# Main.net
KiCad netlist of a schematic drawn in Altium Designer
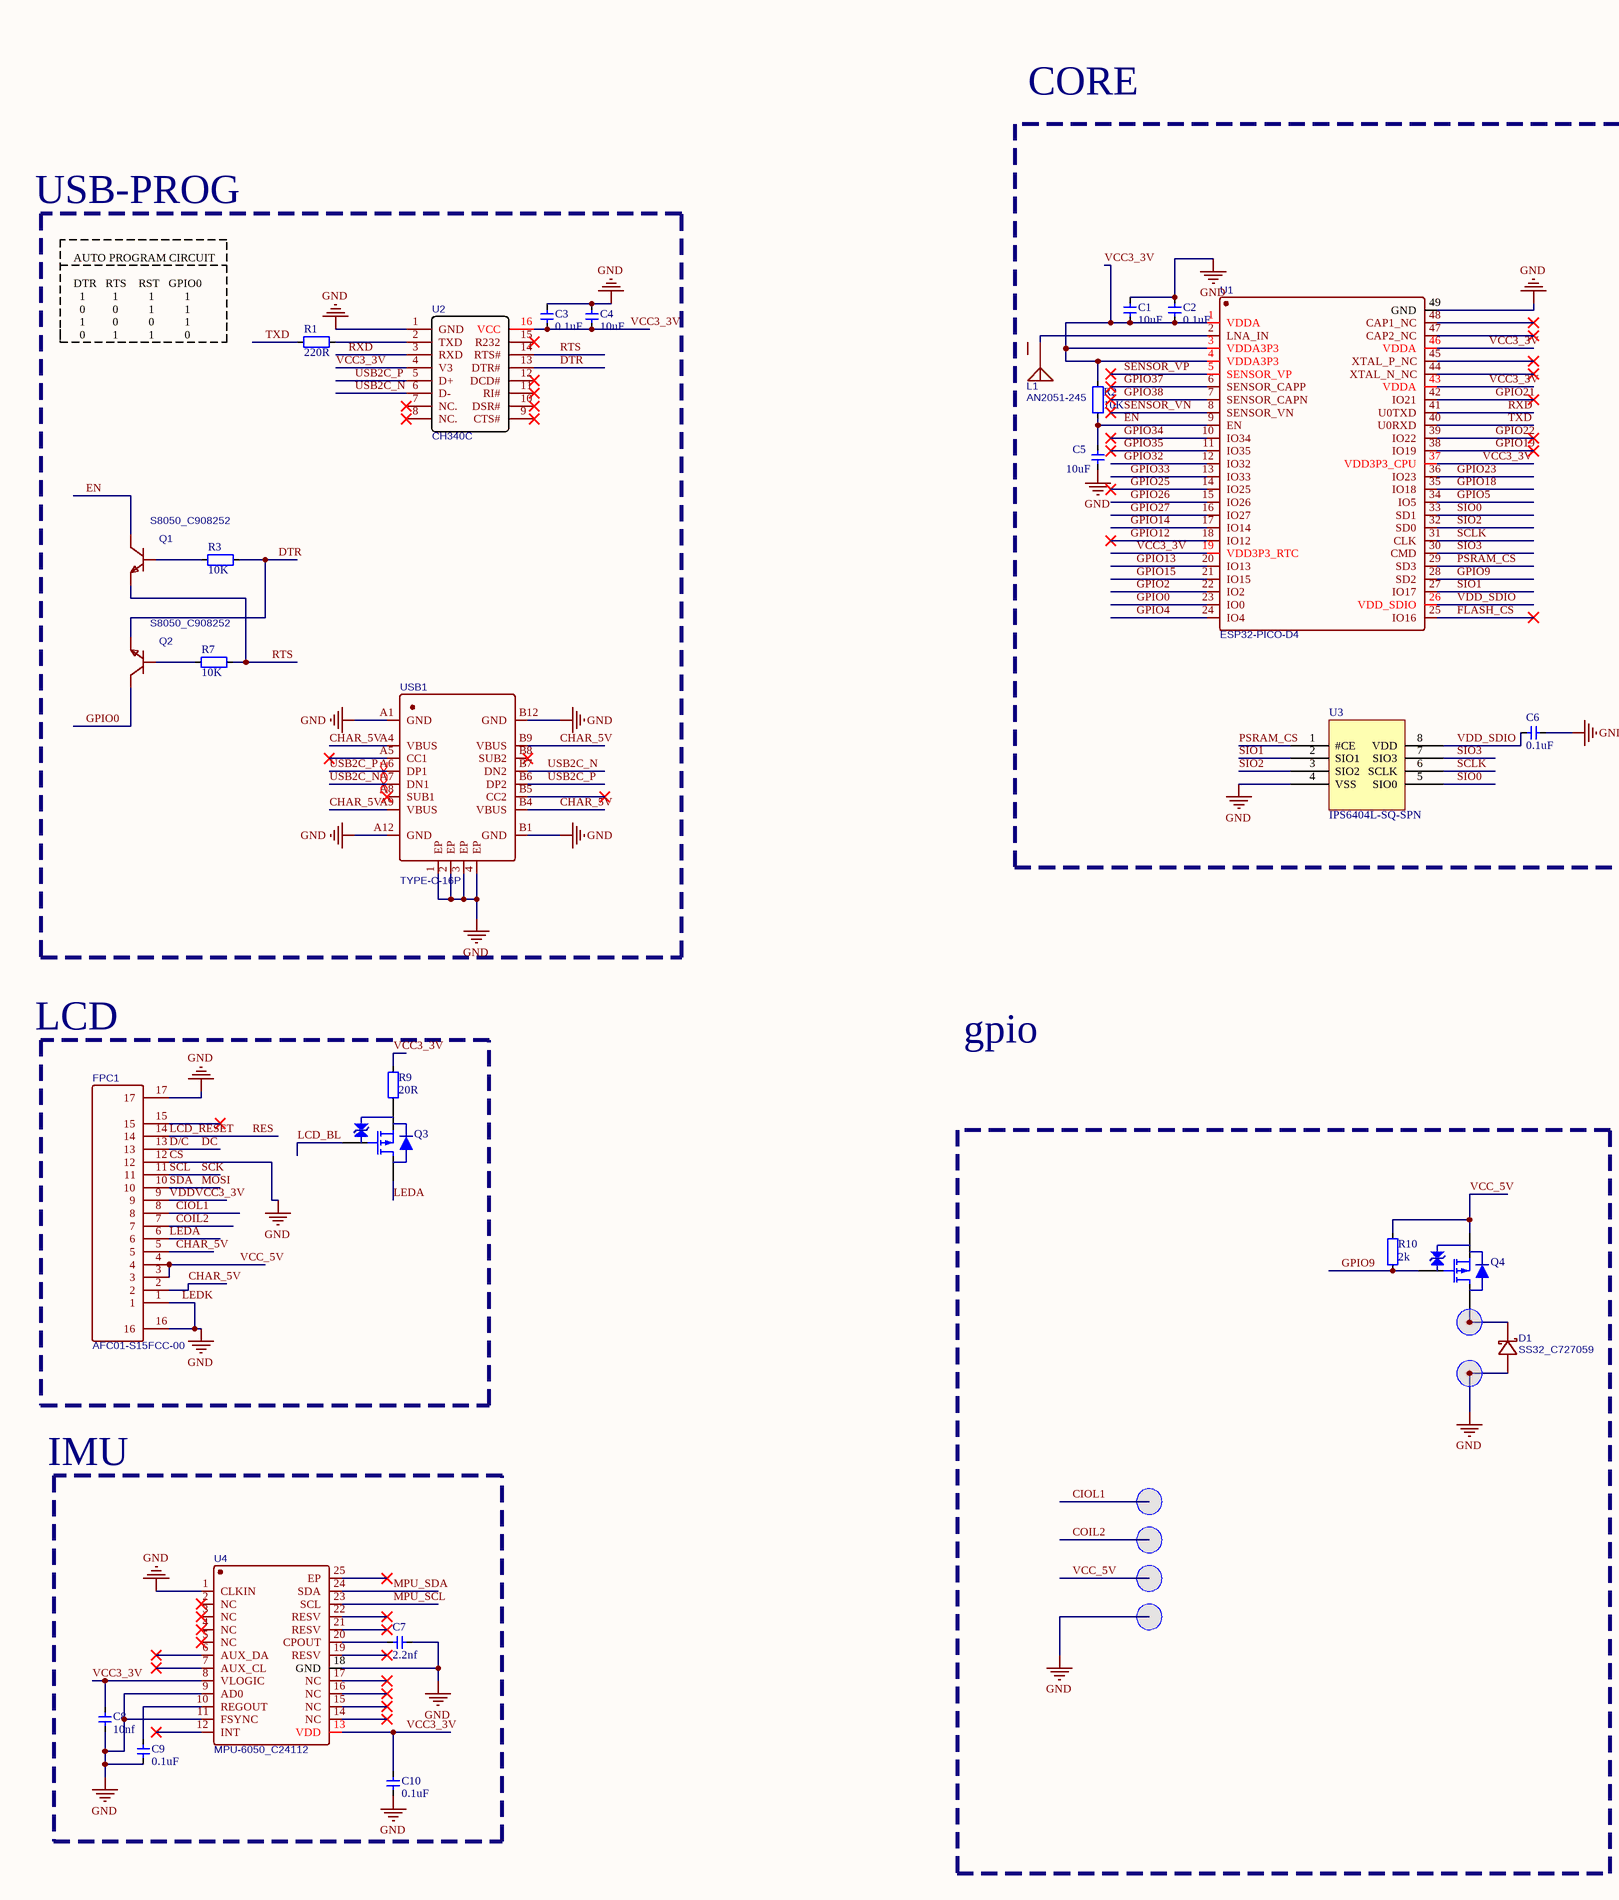
[diagram p0: Main.SchDoc, left]
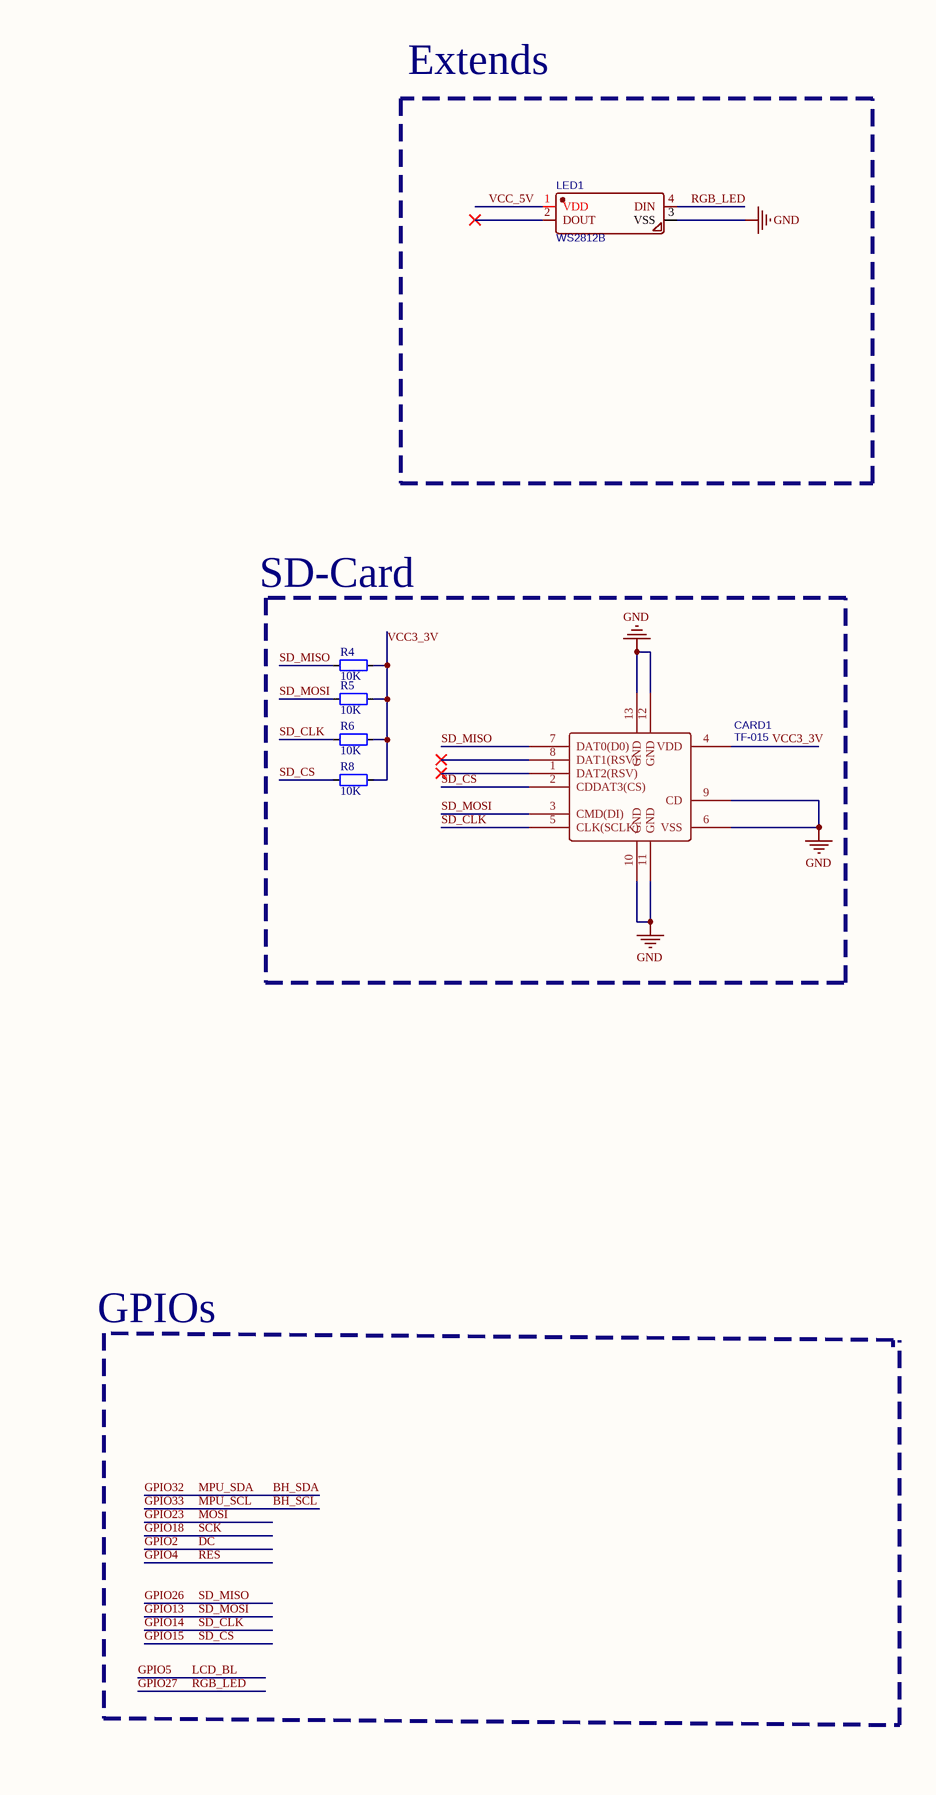
[diagram p1: Main.SchDoc, right]

(export (version "E")
  (design (tool "Eeschema 10.0.6"))
  (components
    (comp (ref "C1")
      (value "10uF")
      (footprint "CAP_0402")
      (description "Capacitor")
      (libsource (lib "BASE") (part "电容-0402"))
    )
    (comp (ref "C2")
      (value "0.1uF")
      (footprint "CAP_0402")
      (description "Capacitor")
      (libsource (lib "BASE") (part "电容-0402"))
    )
    (comp (ref "C3")
      (value "0.1uF")
      (footprint "CAP_0402")
      (description "Capacitor")
      (libsource (lib "BASE") (part "电容-0402"))
    )
    (comp (ref "C4")
      (value "10uF")
      (footprint "CAP_0402")
      (description "Capacitor")
      (libsource (lib "BASE") (part "电容-0402"))
    )
    (comp (ref "C5")
      (value "10uF")
      (footprint "CAP_0402")
      (description "Capacitor")
      (libsource (lib "BASE") (part "电容-0402"))
    )
    (comp (ref "C6")
      (value "0.1uF")
      (footprint "CAP_0402")
      (description "Capacitor")
      (libsource (lib "BASE") (part "电容-0402"))
    )
    (comp (ref "C7")
      (value "2.2nf")
      (footprint "CAP_0402")
      (description "Capacitor")
      (libsource (lib "BASE") (part "电容-0402"))
    )
    (comp (ref "C8")
      (value "10nf")
      (footprint "CAP_0402")
      (description "Capacitor")
      (libsource (lib "BASE") (part "电容-0402"))
    )
    (comp (ref "C9")
      (value "0.1uF")
      (footprint "CAP_0402")
      (description "Capacitor")
      (libsource (lib "BASE") (part "电容-0402"))
    )
    (comp (ref "C10")
      (value "0.1uF")
      (footprint "CAP_0402")
      (description "Capacitor")
      (libsource (lib "BASE") (part "电容-0402"))
    )
    (comp (ref "CARD1")
      (value "TF-015")
      (footprint "TF-SMD_TF-015")
      (fields (field (name "BOM_SUPPLIER PART") "C113206"))
      (libsource (lib "接插件") (part "TF卡座-015"))
    )
    (comp (ref "D1")
      (value "SS32_C727059")
      (footprint "SMAF_L4.3-W2.5-LS5.0-RD")
      (fields
        (field (name "BOM_SUPPLIER PART") "C727059")
        (field (name "BOM_MANUFACTURER PART") "SS32")
        (field (name "CONTRIBUTOR") "LCSC")
      )
      (libsource (lib "BASE") (part "SS32_C727059"))
    )
    (comp (ref "FPC1")
      (value "AFC01-S15FCC-00")
      (footprint "FPC-SMD_AFC01-S15FCC-00")
      (fields (field (name "BOM_SUPPLIER PART") "C262271") (field (name "CONTRIBUTOR") "LCSC"))
      (libsource (lib "接插件") (part "FPC-15P-0.5-AFC01-S15FCC-00"))
    )
    (comp (ref "L1")
      (value "AN2051-245")
      (footprint "ANT2051")
      (fields (field (name "BOM_SUPPLIER PART") "C99727"))
      (libsource (lib "其他") (part "WIFI天线-AN2051-245"))
    )
    (comp (ref "LED1")
      (value "WS2812B")
      (footprint "LED-SMD_4P-L5.0-W5.0-TL")
      (description "RGB灯单线控制")
      (fields (field (name "BOM_SUPPLIER PART") "C114585") (field (name "CONTRIBUTOR") "LCSC"))
      (libsource (lib "MCU") (part "WS2812B"))
    )
    (comp (ref "Q1")
      (value "S8050_C908252")
      (footprint "SOT-23-3_L2.9-W1.3-P1.90-LS2.4-BR")
      (fields
        (field (name "BOM_SUPPLIER PART") "C908252")
        (field (name "BOM_MANUFACTURER PART") "S8050")
        (field (name "CONTRIBUTOR") "LCSC")
      )
      (libsource (lib "BASE") (part "三极管-贴片-S8050_C908252"))
    )
    (comp (ref "Q2")
      (value "S8050_C908252")
      (footprint "SOT-23-3_L2.9-W1.3-P1.90-LS2.4-BR")
      (fields
        (field (name "BOM_SUPPLIER PART") "C908252")
        (field (name "BOM_MANUFACTURER PART") "S8050")
        (field (name "CONTRIBUTOR") "LCSC")
      )
      (libsource (lib "BASE") (part "三极管-贴片-S8050_C908252"))
    )
    (comp (ref "Q3")
      (value "AO3415A")
      (footprint "SOT23-3")
      (description "MOSFET")
      (fields (field (name "PUBLISHER") "Altium Limited"))
      (libsource (lib "BASE") (part "MOS管-P-AO3415A"))
    )
    (comp (ref "Q4")
      (value "AO3415A")
      (footprint "SOT23-3")
      (description "MOSFET")
      (fields (field (name "PUBLISHER") "Altium Limited"))
      (libsource (lib "BASE") (part "MOS管-P-AO3415A"))
    )
    (comp (ref "R1")
      (value "220R")
      (footprint "RES_0402")
      (description "Resistor")
      (libsource (lib "") (part "电阻-0402_2"))
    )
    (comp (ref "R2")
      (value "10K")
      (footprint "RES_0402")
      (description "Resistor")
      (libsource (lib "") (part "电阻-0402_1"))
    )
    (comp (ref "R3")
      (value "10K")
      (footprint "RES_0402")
      (description "Resistor")
      (libsource (lib "") (part "电阻-0402_2"))
    )
    (comp (ref "R4")
      (value "10K")
      (footprint "RES_0402")
      (description "Resistor")
      (libsource (lib "BASE") (part "电阻-0402"))
    )
    (comp (ref "R5")
      (value "10K")
      (footprint "RES_0402")
      (description "Resistor")
      (libsource (lib "BASE") (part "电阻-0402"))
    )
    (comp (ref "R6")
      (value "10K")
      (footprint "RES_0402")
      (description "Resistor")
      (libsource (lib "BASE") (part "电阻-0402"))
    )
    (comp (ref "R7")
      (value "10K")
      (footprint "RES_0402")
      (description "Resistor")
      (libsource (lib "") (part "电阻-0402_2"))
    )
    (comp (ref "R8")
      (value "10K")
      (footprint "RES_0402")
      (description "Resistor")
      (libsource (lib "BASE") (part "电阻-0402"))
    )
    (comp (ref "R9")
      (value "20R")
      (footprint "RES_0402")
      (description "Resistor")
      (libsource (lib "") (part "电阻-0402_1"))
    )
    (comp (ref "R10")
      (value "2k")
      (footprint "RES_0402")
      (description "Resistor")
      (libsource (lib "") (part "电阻-0402_1"))
    )
    (comp (ref "T1") (value "测试点") (footprint "TEST_PT") (libsource (lib "BASE") (part "测试点")))
    (comp (ref "T2") (value "测试点") (footprint "TEST_PT") (libsource (lib "BASE") (part "测试点")))
    (comp (ref "T3") (value "测试点") (footprint "TEST_PT") (libsource (lib "BASE") (part "测试点")))
    (comp (ref "T4") (value "测试点") (footprint "TEST_PT") (libsource (lib "BASE") (part "测试点")))
    (comp (ref "T5") (value "测试点") (footprint "TEST_PT") (libsource (lib "BASE") (part "测试点")))
    (comp (ref "T6") (value "测试点") (footprint "TEST_PT") (libsource (lib "BASE") (part "测试点")))
    (comp (ref "U1")
      (value "ESP32-PICO-D4")
      (footprint "QFN-48_L7.0-W7.0-P0.50-BL-EP5.1")
      (fields (field (name "BOM_SUPPLIER PART") "C193707") (field (name "CONTRIBUTOR") "LCSC"))
      (libsource (lib "MCU") (part "ESP32-PICO-D4"))
    )
    (comp (ref "U2")
      (value "CH340C")
      (footprint "SOP-16_L10.0-W3.9-P1.27-LS6.0-BL")
      (fields (field (name "BOM_SUPPLIER PART") "C84681"))
      (libsource (lib "MCU") (part "CH340C"))
    )
    (comp (ref "U3")
      (value "IPS6404L-SQ-SPN")
      (footprint "SOIC-8_L5.0-W4.0-P1.27-LS6.0-BL-EP")
      (description "psram 8m")
      (libsource (lib "MCU") (part "IPS6404L-SQ-SPN"))
    )
    (comp (ref "U4")
      (value "MPU-6050_C24112")
      (footprint "QFN-24_L4.0-W4.0-P0.50-BL-EP2.6")
      (fields (field (name "BOM_MANUFACTURER PART") "MPU-6050") (field (name "BOM_SUPPLIER PART") "C24112"))
      (libsource (lib "MCU") (part "MPU-6050_C24112"))
    )
    (comp (ref "USB1")
      (value "TYPE-C-16P")
      (footprint "USB-C-SMD_KH-TYPE-C-16P")
      (fields
        (field (name "BOM_SUPPLIER PART") "C709357")
        (field (name "BOM_MANUFACTURER PART") "KH-TYPE-C-16P")
        (field (name "CONTRIBUTOR") "LCSC")
      )
      (libsource (lib "接插件") (part "USBC母座-16P"))
    )
  )
  (nets
    (net (code "1") (name "/BH_SCL") (class "Default")
      (node (ref "U1") (pin "13") (pinfunction "IO33_13") (pintype "passive"))
      (node (ref "U4") (pin "23") (pinfunction "SCL_23") (pintype "passive"))
    )
    (net (code "2") (name "/BH_SDA") (class "Default")
      (node (ref "U1") (pin "12") (pinfunction "IO32_12") (pintype "passive"))
      (node (ref "U4") (pin "24") (pinfunction "SDA_24") (pintype "passive"))
    )
    (net (code "3") (name "/CHAR_5V") (class "Default")
      (node (ref "FPC1") (pin "2") (pinfunction "2_2") (pintype "passive"))
      (node (ref "FPC1") (pin "5") (pinfunction "5_5") (pintype "passive"))
      (node (ref "USB1") (pin "A4") (pinfunction "VBUS_A4") (pintype "passive"))
      (node (ref "USB1") (pin "A9") (pinfunction "VBUS_A9") (pintype "passive"))
      (node (ref "USB1") (pin "B4") (pinfunction "VBUS_B4") (pintype "passive"))
      (node (ref "USB1") (pin "B9") (pinfunction "VBUS_B9") (pintype "passive"))
    )
    (net (code "4") (name "/CIOL1") (class "Default")
      (node (ref "FPC1") (pin "8") (pinfunction "8_8") (pintype "passive"))
      (node (ref "T3") (pin "0") (pinfunction "0_0") (pintype "passive"))
    )
    (net (code "5") (name "/COIL2") (class "Default")
      (node (ref "FPC1") (pin "7") (pinfunction "7_7") (pintype "passive"))
      (node (ref "T4") (pin "0") (pinfunction "0_0") (pintype "passive"))
    )
    (net (code "6") (name "/DC") (class "Default")
      (node (ref "FPC1") (pin "13") (pinfunction "13_13") (pintype "passive"))
      (node (ref "U1") (pin "22") (pinfunction "IO2_22") (pintype "passive"))
    )
    (net (code "7") (name "/DTR") (class "Default")
      (node (ref "Q2") (pin "2") (pinfunction "E_2") (pintype "passive"))
      (node (ref "R3") (pin "1") (pinfunction "1_1") (pintype "passive"))
      (node (ref "U2") (pin "13") (pinfunction "DTR#_13") (pintype "passive"))
    )
    (net (code "8") (name "/EN") (class "Default")
      (node (ref "C5") (pin "2") (pinfunction "2_2") (pintype "passive"))
      (node (ref "Q1") (pin "3") (pinfunction "C_3") (pintype "passive"))
      (node (ref "R2") (pin "1") (pinfunction "1_1") (pintype "passive"))
      (node (ref "U1") (pin "9") (pinfunction "EN_9") (pintype "passive"))
    )
    (net (code "9") (name "/FLASH_CS") (class "Default")
      (node (ref "U1") (pin "25") (pinfunction "IO16_25") (pintype "passive+no_connect"))
    )
    (net (code "10") (name "/GPIO0") (class "Default")
      (node (ref "Q2") (pin "3") (pinfunction "C_3") (pintype "passive"))
      (node (ref "U1") (pin "23") (pinfunction "IO0_23") (pintype "passive"))
    )
    (net (code "11") (name "/GPIO4") (class "Default")
      (node (ref "FPC1") (pin "14") (pinfunction "14_14") (pintype "passive"))
      (node (ref "U1") (pin "24") (pinfunction "IO4_24") (pintype "passive"))
    )
    (net (code "12") (name "/GPIO5") (class "Default")
      (node (ref "Q3") (pin "1") (pinfunction "G_1") (pintype "passive"))
      (node (ref "U1") (pin "34") (pinfunction "IO5_34") (pintype "passive"))
    )
    (net (code "13") (name "/GPIO9") (class "Default")
      (node (ref "Q4") (pin "1") (pinfunction "G_1") (pintype "passive"))
      (node (ref "R10") (pin "1") (pinfunction "1_1") (pintype "passive"))
      (node (ref "U1") (pin "28") (pinfunction "SD2_28") (pintype "passive"))
    )
    (net (code "14") (name "/GPIO12") (class "Default")
      (node (ref "U1") (pin "18") (pinfunction "IO12_18") (pintype "passive+no_connect"))
    )
    (net (code "15") (name "/GPIO13") (class "Default")
      (node (ref "CARD1") (pin "3") (pinfunction "CMD(DI)_3") (pintype "passive"))
      (node (ref "R5") (pin "1") (pinfunction "1_1") (pintype "passive"))
      (node (ref "U1") (pin "20") (pinfunction "IO13_20") (pintype "passive"))
    )
    (net (code "16") (name "/GPIO14") (class "Default")
      (node (ref "CARD1") (pin "5") (pinfunction "CLK(SCLK)_5") (pintype "passive"))
      (node (ref "R6") (pin "1") (pinfunction "1_1") (pintype "passive"))
      (node (ref "U1") (pin "17") (pinfunction "IO14_17") (pintype "passive"))
    )
    (net (code "17") (name "/GPIO15") (class "Default")
      (node (ref "CARD1") (pin "2") (pinfunction "CDDAT3(CS)_2") (pintype "passive"))
      (node (ref "R8") (pin "1") (pinfunction "1_1") (pintype "passive"))
      (node (ref "U1") (pin "21") (pinfunction "IO15_21") (pintype "passive"))
    )
    (net (code "18") (name "/GPIO18") (class "Default")
      (node (ref "FPC1") (pin "11") (pinfunction "11_11") (pintype "passive"))
      (node (ref "U1") (pin "35") (pinfunction "IO18_35") (pintype "passive"))
    )
    (net (code "19") (name "/GPIO19") (class "Default")
      (node (ref "U1") (pin "38") (pinfunction "IO19_38") (pintype "passive+no_connect"))
    )
    (net (code "20") (name "/GPIO21") (class "Default")
      (node (ref "U1") (pin "42") (pinfunction "IO21_42") (pintype "passive+no_connect"))
    )
    (net (code "21") (name "/GPIO22") (class "Default")
      (node (ref "U1") (pin "39") (pinfunction "IO22_39") (pintype "passive+no_connect"))
    )
    (net (code "22") (name "/GPIO23") (class "Default")
      (node (ref "FPC1") (pin "10") (pinfunction "10_10") (pintype "passive"))
      (node (ref "U1") (pin "36") (pinfunction "IO23_36") (pintype "passive"))
    )
    (net (code "23") (name "/GPIO25") (class "Default")
      (node (ref "U1") (pin "14") (pinfunction "IO25_14") (pintype "passive+no_connect"))
    )
    (net (code "24") (name "/GPIO26") (class "Default")
      (node (ref "CARD1") (pin "7") (pinfunction "DAT0(D0)_7") (pintype "passive"))
      (node (ref "R4") (pin "1") (pinfunction "1_1") (pintype "passive"))
      (node (ref "U1") (pin "15") (pinfunction "IO26_15") (pintype "passive"))
    )
    (net (code "25") (name "/GPIO27") (class "Default")
      (node (ref "LED1") (pin "4") (pinfunction "DIN_4") (pintype "passive"))
      (node (ref "U1") (pin "16") (pinfunction "IO27_16") (pintype "passive"))
    )
    (net (code "26") (name "/GPIO34") (class "Default")
      (node (ref "U1") (pin "10") (pinfunction "IO34_10") (pintype "passive+no_connect"))
    )
    (net (code "27") (name "/GPIO35") (class "Default")
      (node (ref "U1") (pin "11") (pinfunction "IO35_11") (pintype "passive+no_connect"))
    )
    (net (code "28") (name "/GPIO37") (class "Default")
      (node (ref "U1") (pin "6") (pinfunction "SENSOR_CAPP_6") (pintype "passive+no_connect"))
    )
    (net (code "29") (name "/GPIO38") (class "Default")
      (node (ref "U1") (pin "7") (pinfunction "SENSOR_CAPN_7") (pintype "passive+no_connect"))
    )
    (net (code "30") (name "/LEDA") (class "Default")
      (node (ref "FPC1") (pin "6") (pinfunction "6_6") (pintype "passive"))
      (node (ref "Q3") (pin "3") (pinfunction "D_3") (pintype "passive"))
    )
    (net (code "31") (name "/PSRAM_CS") (class "Default")
      (node (ref "U1") (pin "29") (pinfunction "SD3_29") (pintype "passive"))
      (node (ref "U3") (pin "1") (pinfunction "#CE_1") (pintype "passive"))
    )
    (net (code "32") (name "/RTS") (class "Default")
      (node (ref "Q1") (pin "2") (pinfunction "E_2") (pintype "passive"))
      (node (ref "R7") (pin "1") (pinfunction "1_1") (pintype "passive"))
      (node (ref "U2") (pin "14") (pinfunction "RTS#_14") (pintype "passive"))
    )
    (net (code "33") (name "/RXD") (class "Default")
      (node (ref "U1") (pin "41") (pinfunction "U0TXD_41") (pintype "passive"))
      (node (ref "U2") (pin "3") (pinfunction "RXD_3") (pintype "passive"))
    )
    (net (code "34") (name "/SCLK") (class "Default")
      (node (ref "U1") (pin "31") (pinfunction "CLK_31") (pintype "passive"))
      (node (ref "U3") (pin "6") (pinfunction "SCLK_6") (pintype "passive"))
    )
    (net (code "35") (name "/SENSOR_VN") (class "Default")
      (node (ref "U1") (pin "8") (pinfunction "SENSOR_VN_8") (pintype "passive+no_connect"))
    )
    (net (code "36") (name "/SENSOR_VP") (class "Default")
      (node (ref "U1") (pin "5") (pinfunction "SENSOR_VP_5") (pintype "passive+no_connect"))
    )
    (net (code "37") (name "/SIO0") (class "Default")
      (node (ref "U1") (pin "33") (pinfunction "SD1_33") (pintype "passive"))
      (node (ref "U3") (pin "5") (pinfunction "SIO0_5") (pintype "passive"))
    )
    (net (code "38") (name "/SIO1") (class "Default")
      (node (ref "U1") (pin "27") (pinfunction "IO17_27") (pintype "passive"))
      (node (ref "U3") (pin "2") (pinfunction "SIO1_2") (pintype "passive"))
    )
    (net (code "39") (name "/SIO2") (class "Default")
      (node (ref "U1") (pin "32") (pinfunction "SD0_32") (pintype "passive"))
      (node (ref "U3") (pin "3") (pinfunction "SIO2_3") (pintype "passive"))
    )
    (net (code "40") (name "/SIO3") (class "Default")
      (node (ref "U1") (pin "30") (pinfunction "CMD_30") (pintype "passive"))
      (node (ref "U3") (pin "7") (pinfunction "SIO3_7") (pintype "passive"))
    )
    (net (code "41") (name "/TXD") (class "Default")
      (node (ref "R1") (pin "2") (pinfunction "2_2") (pintype "passive"))
      (node (ref "U1") (pin "40") (pinfunction "U0RXD_40") (pintype "passive"))
    )
    (net (code "42") (name "/USB2C_N") (class "Default")
      (node (ref "U2") (pin "6") (pinfunction "D-_6") (pintype "passive"))
      (node (ref "USB1") (pin "A7") (pinfunction "DN1_A7") (pintype "passive"))
      (node (ref "USB1") (pin "B7") (pinfunction "DN2_B7") (pintype "passive"))
    )
    (net (code "43") (name "/USB2C_P") (class "Default")
      (node (ref "U2") (pin "5") (pinfunction "D+_5") (pintype "passive"))
      (node (ref "USB1") (pin "A6") (pinfunction "DP1_A6") (pintype "passive"))
      (node (ref "USB1") (pin "B6") (pinfunction "DP2_B6") (pintype "passive"))
    )
    (net (code "44") (name "/VCC3_3V") (class "Default")
      (node (ref "C1") (pin "1") (pinfunction "1_1") (pintype "passive"))
      (node (ref "C10") (pin "1") (pinfunction "1_1") (pintype "passive"))
      (node (ref "C2") (pin "1") (pinfunction "1_1") (pintype "passive"))
      (node (ref "C3") (pin "1") (pinfunction "1_1") (pintype "passive"))
      (node (ref "C4") (pin "1") (pinfunction "1_1") (pintype "passive"))
      (node (ref "C8") (pin "1") (pinfunction "1_1") (pintype "passive"))
      (node (ref "CARD1") (pin "4") (pinfunction "VDD_4") (pintype "passive"))
      (node (ref "FPC1") (pin "9") (pinfunction "9_9") (pintype "passive"))
      (node (ref "R2") (pin "2") (pinfunction "2_2") (pintype "passive"))
      (node (ref "R4") (pin "2") (pinfunction "2_2") (pintype "passive"))
      (node (ref "R5") (pin "2") (pinfunction "2_2") (pintype "passive"))
      (node (ref "R6") (pin "2") (pinfunction "2_2") (pintype "passive"))
      (node (ref "R8") (pin "2") (pinfunction "2_2") (pintype "passive"))
      (node (ref "R9") (pin "2") (pinfunction "2_2") (pintype "passive"))
      (node (ref "U1") (pin "1") (pinfunction "VDDA_1") (pintype "passive"))
      (node (ref "U1") (pin "19") (pinfunction "VDD3P3_RTC_19") (pintype "passive"))
      (node (ref "U1") (pin "3") (pinfunction "VDDA3P3_3") (pintype "passive"))
      (node (ref "U1") (pin "37") (pinfunction "VDD3P3_CPU_37") (pintype "passive"))
      (node (ref "U1") (pin "4") (pinfunction "VDDA3P3_4") (pintype "passive"))
      (node (ref "U1") (pin "43") (pinfunction "VDDA_43") (pintype "passive"))
      (node (ref "U1") (pin "46") (pinfunction "VDDA_46") (pintype "passive"))
      (node (ref "U2") (pin "16") (pinfunction "VCC_16") (pintype "passive"))
      (node (ref "U2") (pin "4") (pinfunction "V3_4") (pintype "passive"))
      (node (ref "U4") (pin "13") (pinfunction "VDD_13") (pintype "passive"))
      (node (ref "U4") (pin "8") (pinfunction "VLOGIC_8") (pintype "passive"))
    )
    (net (code "45") (name "/VCC_5V") (class "Default")
      (node (ref "FPC1") (pin "3") (pinfunction "3_3") (pintype "passive"))
      (node (ref "FPC1") (pin "4") (pinfunction "4_4") (pintype "passive"))
      (node (ref "LED1") (pin "1") (pinfunction "VDD_1") (pintype "passive"))
      (node (ref "Q4") (pin "2") (pinfunction "S_2") (pintype "passive"))
      (node (ref "R10") (pin "2") (pinfunction "2_2") (pintype "passive"))
      (node (ref "T5") (pin "0") (pinfunction "0_0") (pintype "passive"))
    )
    (net (code "46") (name "/VDD_SDIO") (class "Default")
      (node (ref "C6") (pin "1") (pinfunction "1_1") (pintype "passive"))
      (node (ref "U1") (pin "26") (pinfunction "VDD_SDIO_26") (pintype "passive"))
      (node (ref "U3") (pin "8") (pinfunction "VDD_8") (pintype "passive"))
    )
    (net (code "47") (name "GND") (class "Default")
      (node (ref "C1") (pin "2") (pinfunction "2_2") (pintype "passive"))
      (node (ref "C10") (pin "2") (pinfunction "2_2") (pintype "passive"))
      (node (ref "C2") (pin "2") (pinfunction "2_2") (pintype "passive"))
      (node (ref "C3") (pin "2") (pinfunction "2_2") (pintype "passive"))
      (node (ref "C4") (pin "2") (pinfunction "2_2") (pintype "passive"))
      (node (ref "C5") (pin "1") (pinfunction "1_1") (pintype "passive"))
      (node (ref "C6") (pin "2") (pinfunction "2_2") (pintype "passive"))
      (node (ref "C7") (pin "2") (pinfunction "2_2") (pintype "passive"))
      (node (ref "C8") (pin "2") (pinfunction "2_2") (pintype "passive"))
      (node (ref "C9") (pin "2") (pinfunction "2_2") (pintype "passive"))
      (node (ref "CARD1") (pin "10") (pinfunction "GND_10") (pintype "passive"))
      (node (ref "CARD1") (pin "11") (pinfunction "GND_11") (pintype "passive"))
      (node (ref "CARD1") (pin "12") (pinfunction "GND_12") (pintype "passive"))
      (node (ref "CARD1") (pin "13") (pinfunction "GND_13") (pintype "passive"))
      (node (ref "CARD1") (pin "6") (pinfunction "VSS_6") (pintype "passive"))
      (node (ref "CARD1") (pin "9") (pinfunction "CD_9") (pintype "passive"))
      (node (ref "D1") (pin "2") (pinfunction "A_2") (pintype "passive"))
      (node (ref "FPC1") (pin "1") (pinfunction "1_1") (pintype "passive"))
      (node (ref "FPC1") (pin "12") (pinfunction "12_12") (pintype "passive"))
      (node (ref "FPC1") (pin "16") (pinfunction "16_16") (pintype "passive"))
      (node (ref "FPC1") (pin "17") (pinfunction "17_17") (pintype "passive"))
      (node (ref "LED1") (pin "3") (pinfunction "VSS_3") (pintype "passive"))
      (node (ref "T2") (pin "0") (pinfunction "0_0") (pintype "passive"))
      (node (ref "T6") (pin "0") (pinfunction "0_0") (pintype "passive"))
      (node (ref "U1") (pin "49") (pinfunction "GND_49") (pintype "passive"))
      (node (ref "U2") (pin "1") (pinfunction "GND_1") (pintype "passive"))
      (node (ref "U3") (pin "4") (pinfunction "VSS_4") (pintype "passive"))
      (node (ref "U4") (pin "1") (pinfunction "CLKIN_1") (pintype "passive"))
      (node (ref "U4") (pin "11") (pinfunction "FSYNC_11") (pintype "passive"))
      (node (ref "U4") (pin "18") (pinfunction "GND_18") (pintype "passive"))
      (node (ref "U4") (pin "9") (pinfunction "AD0_9") (pintype "passive"))
      (node (ref "USB1") (pin "1") (pinfunction "EP_1") (pintype "passive"))
      (node (ref "USB1") (pin "2") (pinfunction "EP_2") (pintype "passive"))
      (node (ref "USB1") (pin "3") (pinfunction "EP_3") (pintype "passive"))
      (node (ref "USB1") (pin "4") (pinfunction "EP_4") (pintype "passive"))
      (node (ref "USB1") (pin "A1") (pinfunction "GND_A1") (pintype "passive"))
      (node (ref "USB1") (pin "A12") (pinfunction "GND_A12") (pintype "passive"))
      (node (ref "USB1") (pin "B1") (pinfunction "GND_B1") (pintype "passive"))
      (node (ref "USB1") (pin "B12") (pinfunction "GND_B12") (pintype "passive"))
    )
    (net (code "48") (name "Net-(D1-C)") (class "Default")
      (node (ref "D1") (pin "1") (pinfunction "C_1") (pintype "passive"))
      (node (ref "Q4") (pin "3") (pinfunction "D_3") (pintype "passive"))
      (node (ref "T1") (pin "0") (pinfunction "0_0") (pintype "passive"))
    )
    (net (code "49") (name "Net-(L1-ANT)") (class "Default")
      (node (ref "L1") (pin "1") (pinfunction "ANT_1") (pintype "passive"))
      (node (ref "U1") (pin "2") (pinfunction "LNA_IN_2") (pintype "passive"))
    )
    (net (code "50") (name "Net-(Q1-B)") (class "Default")
      (node (ref "Q1") (pin "1") (pinfunction "B_1") (pintype "passive"))
      (node (ref "R3") (pin "2") (pinfunction "2_2") (pintype "passive"))
    )
    (net (code "51") (name "Net-(Q2-B)") (class "Default")
      (node (ref "Q2") (pin "1") (pinfunction "B_1") (pintype "passive"))
      (node (ref "R7") (pin "2") (pinfunction "2_2") (pintype "passive"))
    )
    (net (code "52") (name "Net-(Q3-S)") (class "Default")
      (node (ref "Q3") (pin "2") (pinfunction "S_2") (pintype "passive"))
      (node (ref "R9") (pin "1") (pinfunction "1_1") (pintype "passive"))
    )
    (net (code "53") (name "Net-(U2-TXD)") (class "Default")
      (node (ref "R1") (pin "1") (pinfunction "1_1") (pintype "passive"))
      (node (ref "U2") (pin "2") (pinfunction "TXD_2") (pintype "passive"))
    )
    (net (code "54") (name "Net-(U4-CPOUT)") (class "Default")
      (node (ref "C7") (pin "1") (pinfunction "1_1") (pintype "passive"))
      (node (ref "U4") (pin "20") (pinfunction "CPOUT_20") (pintype "passive"))
    )
    (net (code "55") (name "Net-(U4-REGOUT)") (class "Default")
      (node (ref "C9") (pin "1") (pinfunction "1_1") (pintype "passive"))
      (node (ref "U4") (pin "10") (pinfunction "REGOUT_10") (pintype "passive"))
    )
    (net (code "56") (name "unconnected-(CARD1-DAT1(RSV)-Pad8)") (class "Default")
      (node (ref "CARD1") (pin "8") (pinfunction "DAT1(RSV)_8") (pintype "passive+no_connect"))
    )
    (net (code "57") (name "unconnected-(CARD1-DAT2(RSV)-Pad1)") (class "Default")
      (node (ref "CARD1") (pin "1") (pinfunction "DAT2(RSV)_1") (pintype "passive+no_connect"))
    )
    (net (code "58") (name "unconnected-(FPC1-Pad15)") (class "Default")
      (node (ref "FPC1") (pin "15") (pinfunction "15_15") (pintype "passive+no_connect"))
    )
    (net (code "59") (name "unconnected-(L1-Pad2)") (class "Default")
      (node (ref "L1") (pin "2") (pinfunction "2_2") (pintype "passive"))
    )
    (net (code "60") (name "unconnected-(LED1-DOUT-Pad2)") (class "Default")
      (node (ref "LED1") (pin "2") (pinfunction "DOUT_2") (pintype "passive+no_connect"))
    )
    (net (code "61") (name "unconnected-(U1-CAP1_NC-Pad48)") (class "Default")
      (node (ref "U1") (pin "48") (pinfunction "CAP1_NC_48") (pintype "passive+no_connect"))
    )
    (net (code "62") (name "unconnected-(U1-CAP2_NC-Pad47)") (class "Default")
      (node (ref "U1") (pin "47") (pinfunction "CAP2_NC_47") (pintype "passive+no_connect"))
    )
    (net (code "63") (name "unconnected-(U1-XTAL_N_NC-Pad44)") (class "Default")
      (node (ref "U1") (pin "44") (pinfunction "XTAL_N_NC_44") (pintype "passive+no_connect"))
    )
    (net (code "64") (name "unconnected-(U1-XTAL_P_NC-Pad45)") (class "Default")
      (node (ref "U1") (pin "45") (pinfunction "XTAL_P_NC_45") (pintype "passive+no_connect"))
    )
    (net (code "65") (name "unconnected-(U2-CTS#-Pad9)") (class "Default")
      (node (ref "U2") (pin "9") (pinfunction "CTS#_9") (pintype "passive+no_connect"))
    )
    (net (code "66") (name "unconnected-(U2-DCD#-Pad12)") (class "Default")
      (node (ref "U2") (pin "12") (pinfunction "DCD#_12") (pintype "passive+no_connect"))
    )
    (net (code "67") (name "unconnected-(U2-DSR#-Pad10)") (class "Default")
      (node (ref "U2") (pin "10") (pinfunction "DSR#_10") (pintype "passive+no_connect"))
    )
    (net (code "68") (name "unconnected-(U2-NC.-Pad7)") (class "Default")
      (node (ref "U2") (pin "7") (pinfunction "NC._7") (pintype "passive+no_connect"))
    )
    (net (code "69") (name "unconnected-(U2-NC.-Pad8)") (class "Default")
      (node (ref "U2") (pin "8") (pinfunction "NC._8") (pintype "passive+no_connect"))
    )
    (net (code "70") (name "unconnected-(U2-R232-Pad15)") (class "Default")
      (node (ref "U2") (pin "15") (pinfunction "R232_15") (pintype "passive+no_connect"))
    )
    (net (code "71") (name "unconnected-(U2-RI#-Pad11)") (class "Default")
      (node (ref "U2") (pin "11") (pinfunction "RI#_11") (pintype "passive+no_connect"))
    )
    (net (code "72") (name "unconnected-(U4-AUX_CL-Pad7)") (class "Default")
      (node (ref "U4") (pin "7") (pinfunction "AUX_CL_7") (pintype "passive+no_connect"))
    )
    (net (code "73") (name "unconnected-(U4-AUX_DA-Pad6)") (class "Default")
      (node (ref "U4") (pin "6") (pinfunction "AUX_DA_6") (pintype "passive+no_connect"))
    )
    (net (code "74") (name "unconnected-(U4-EP-Pad25)") (class "Default")
      (node (ref "U4") (pin "25") (pinfunction "EP_25") (pintype "passive+no_connect"))
    )
    (net (code "75") (name "unconnected-(U4-INT-Pad12)") (class "Default")
      (node (ref "U4") (pin "12") (pinfunction "INT_12") (pintype "passive+no_connect"))
    )
    (net (code "76") (name "unconnected-(U4-NC-Pad2)") (class "Default")
      (node (ref "U4") (pin "2") (pinfunction "NC_2") (pintype "passive+no_connect"))
    )
    (net (code "77") (name "unconnected-(U4-NC-Pad3)") (class "Default")
      (node (ref "U4") (pin "3") (pinfunction "NC_3") (pintype "passive+no_connect"))
    )
    (net (code "78") (name "unconnected-(U4-NC-Pad4)") (class "Default")
      (node (ref "U4") (pin "4") (pinfunction "NC_4") (pintype "passive+no_connect"))
    )
    (net (code "79") (name "unconnected-(U4-NC-Pad5)") (class "Default")
      (node (ref "U4") (pin "5") (pinfunction "NC_5") (pintype "passive+no_connect"))
    )
    (net (code "80") (name "unconnected-(U4-NC-Pad14)") (class "Default")
      (node (ref "U4") (pin "14") (pinfunction "NC_14") (pintype "passive+no_connect"))
    )
    (net (code "81") (name "unconnected-(U4-NC-Pad15)") (class "Default")
      (node (ref "U4") (pin "15") (pinfunction "NC_15") (pintype "passive+no_connect"))
    )
    (net (code "82") (name "unconnected-(U4-NC-Pad16)") (class "Default")
      (node (ref "U4") (pin "16") (pinfunction "NC_16") (pintype "passive+no_connect"))
    )
    (net (code "83") (name "unconnected-(U4-NC-Pad17)") (class "Default")
      (node (ref "U4") (pin "17") (pinfunction "NC_17") (pintype "passive+no_connect"))
    )
    (net (code "84") (name "unconnected-(U4-RESV-Pad19)") (class "Default")
      (node (ref "U4") (pin "19") (pinfunction "RESV_19") (pintype "passive+no_connect"))
    )
    (net (code "85") (name "unconnected-(U4-RESV-Pad21)") (class "Default")
      (node (ref "U4") (pin "21") (pinfunction "RESV_21") (pintype "passive+no_connect"))
    )
    (net (code "86") (name "unconnected-(U4-RESV-Pad22)") (class "Default")
      (node (ref "U4") (pin "22") (pinfunction "RESV_22") (pintype "passive+no_connect"))
    )
    (net (code "87") (name "unconnected-(USB1-CC1-PadA5)") (class "Default")
      (node (ref "USB1") (pin "A5") (pinfunction "CC1_A5") (pintype "passive+no_connect"))
    )
    (net (code "88") (name "unconnected-(USB1-CC2-PadB5)") (class "Default")
      (node (ref "USB1") (pin "B5") (pinfunction "CC2_B5") (pintype "passive+no_connect"))
    )
    (net (code "89") (name "unconnected-(USB1-SUB1-PadA8)") (class "Default")
      (node (ref "USB1") (pin "A8") (pinfunction "SUB1_A8") (pintype "passive+no_connect"))
    )
    (net (code "90") (name "unconnected-(USB1-SUB2-PadB8)") (class "Default")
      (node (ref "USB1") (pin "B8") (pinfunction "SUB2_B8") (pintype "passive+no_connect"))
    )
  )
)
